# 5-Memory.net
KiCad netlist of a schematic drawn in Altium Designer
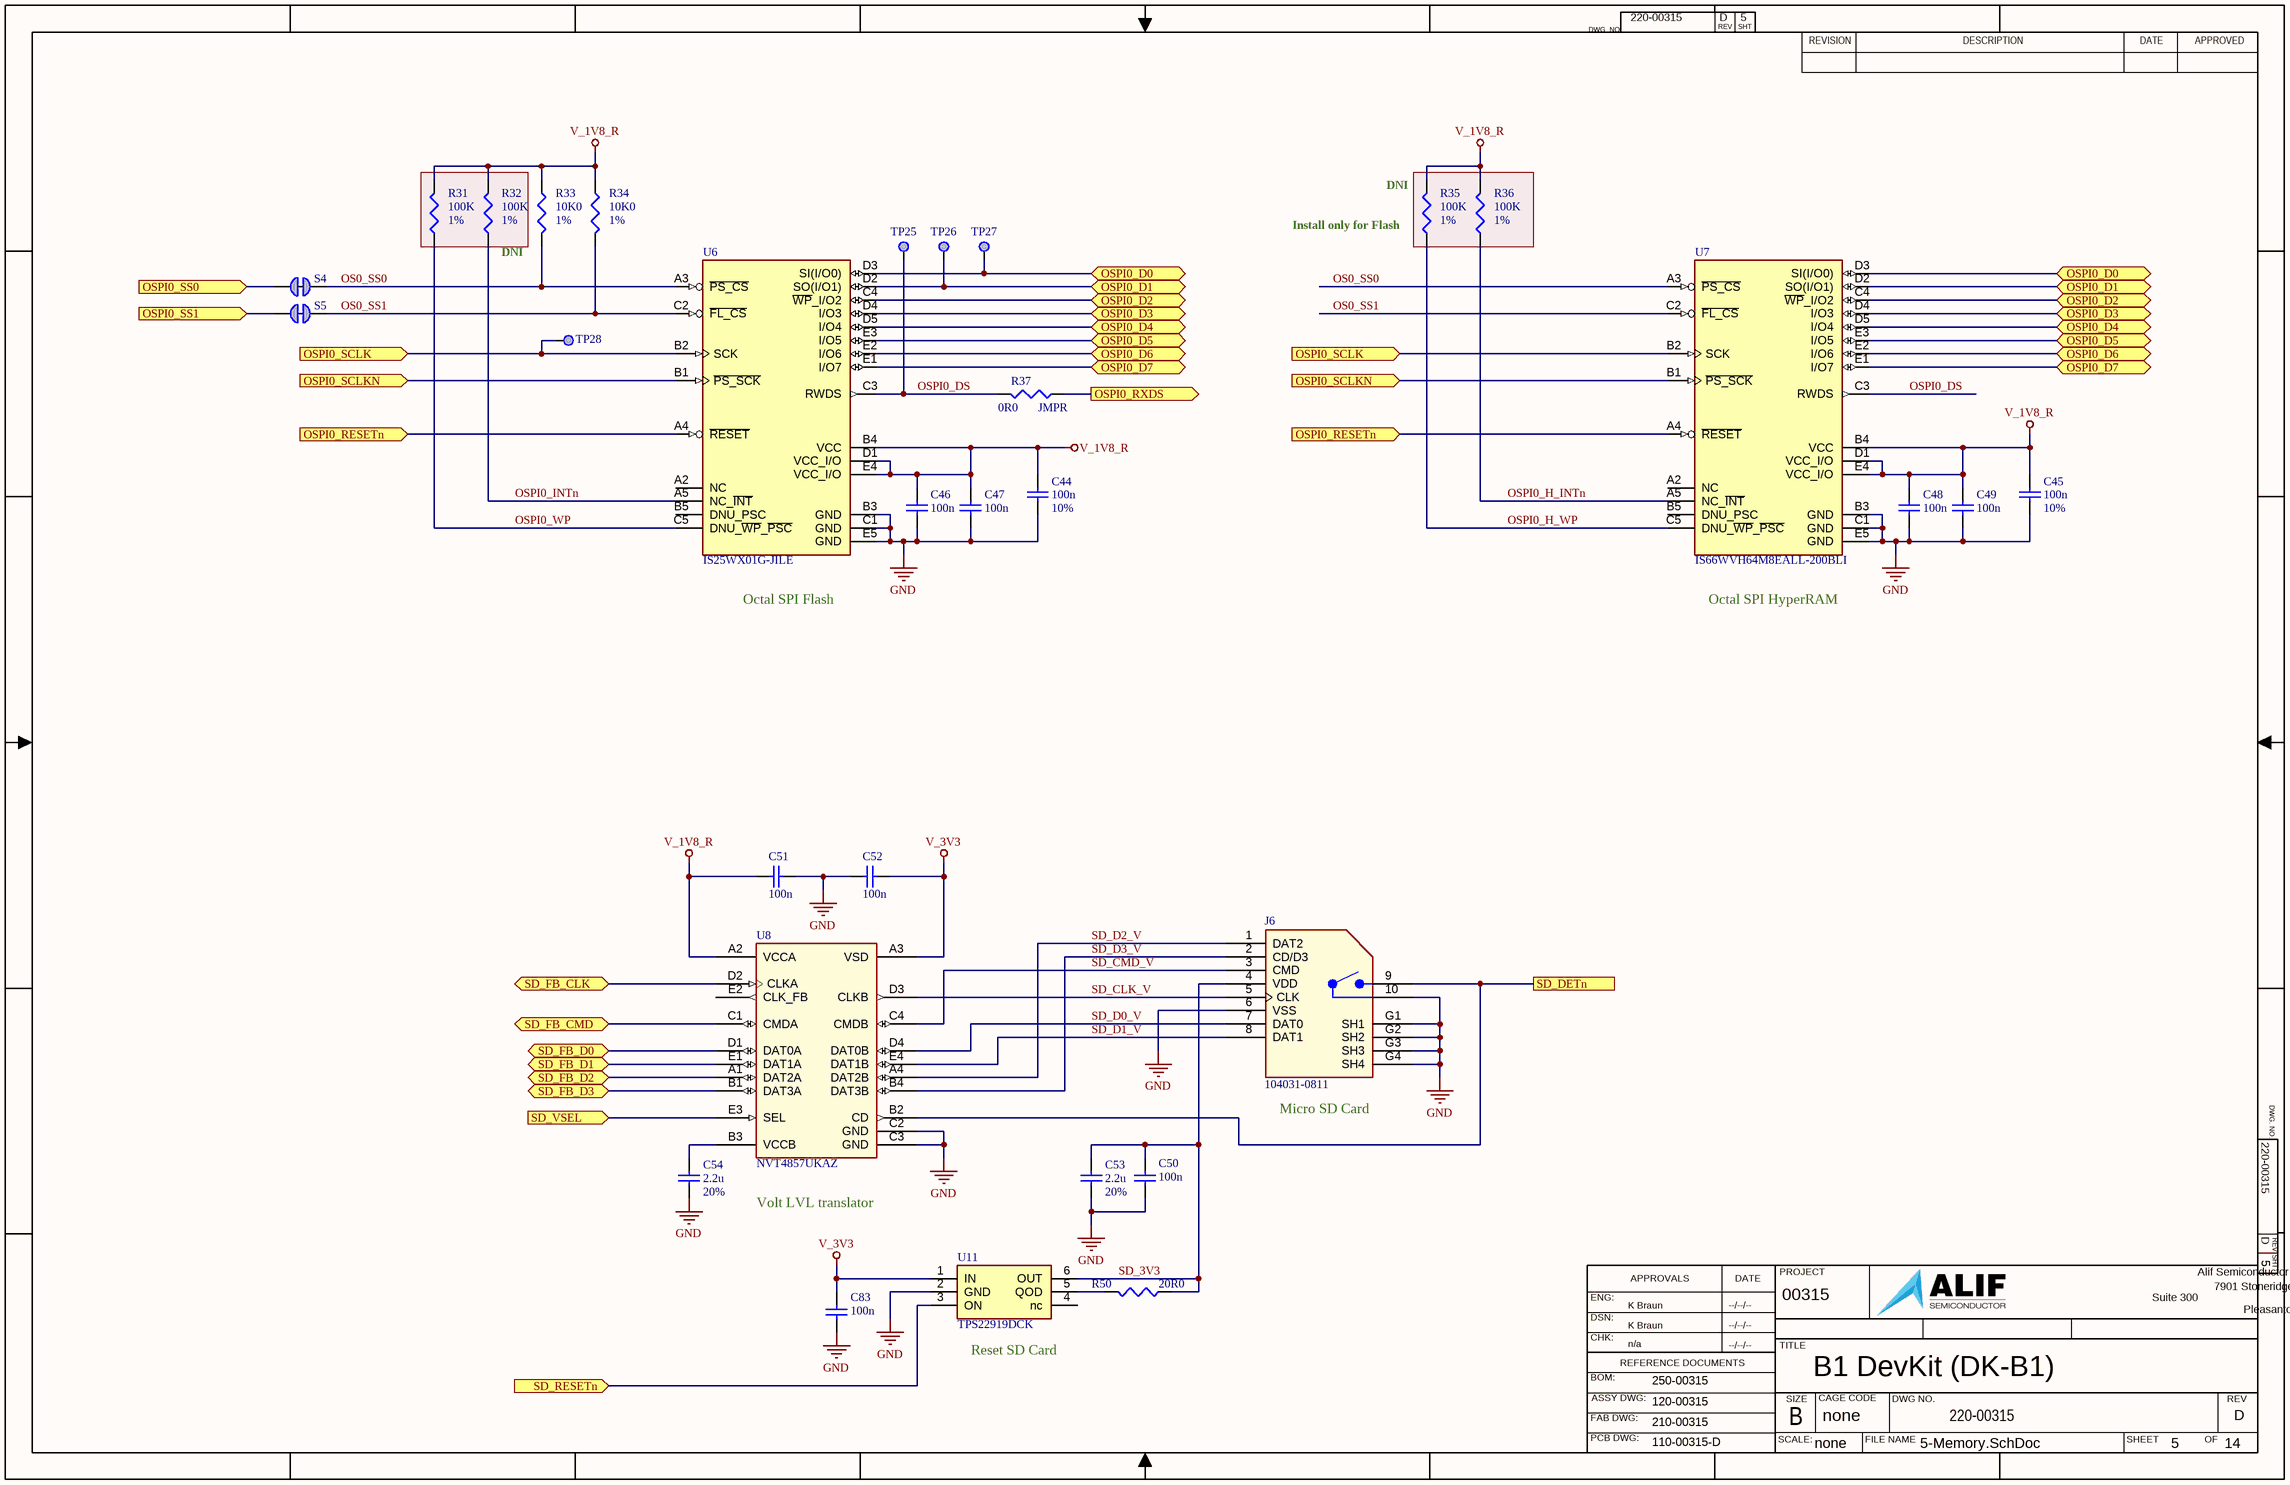
[diagram p0: 5-Memory.SchDoc]

(export (version "E")
  (design (tool "Eeschema 10.0.6"))
  (components
    (comp (ref "C44")
      (value "100n")
      (footprint "CAPC0402-01")
      (description "Cap,100nF,10%,50V,X7R,0402")
      (fields
        (field (name "VOLTAGE") "50V")
        (field (name "TOLERANCE") "10%")
        (field (name "Comment") "Cap")
        (field (name "PUBLISHER") "Altium Limited")
      )
      (libsource (lib "kb1") (part "Cap"))
    )
    (comp (ref "C45")
      (value "100n")
      (footprint "CAPC0402-01")
      (description "Cap,100nF,10%,50V,X7R,0402")
      (fields
        (field (name "VOLTAGE") "50V")
        (field (name "TOLERANCE") "10%")
        (field (name "Comment") "Cap")
        (field (name "PUBLISHER") "Altium Limited")
      )
      (libsource (lib "kb1") (part "Cap"))
    )
    (comp (ref "C46")
      (value "100n")
      (footprint "CAPC0402-01")
      (description "Cap,100nF,10%,50V,X7R,0402")
      (fields
        (field (name "VOLTAGE") "50V")
        (field (name "TOLERANCE") "10%")
        (field (name "PUBLISHER") "Altium Limited")
      )
      (libsource (lib "kb1") (part "Cap"))
    )
    (comp (ref "C47")
      (value "100n")
      (footprint "CAPC0402-01")
      (description "Cap,100nF,10%,50V,X7R,0402")
      (fields
        (field (name "VOLTAGE") "50V")
        (field (name "TOLERANCE") "10%")
        (field (name "PUBLISHER") "Altium Limited")
      )
      (libsource (lib "kb1") (part "Cap"))
    )
    (comp (ref "C48")
      (value "100n")
      (footprint "CAPC0402-01")
      (description "Cap,100nF,10%,50V,X7R,0402")
      (fields
        (field (name "VOLTAGE") "50V")
        (field (name "TOLERANCE") "10%")
        (field (name "PUBLISHER") "Altium Limited")
      )
      (libsource (lib "kb1") (part "Cap"))
    )
    (comp (ref "C49")
      (value "100n")
      (footprint "CAPC0402-01")
      (description "Cap,100nF,10%,50V,X7R,0402")
      (fields
        (field (name "VOLTAGE") "50V")
        (field (name "TOLERANCE") "10%")
        (field (name "PUBLISHER") "Altium Limited")
      )
      (libsource (lib "kb1") (part "Cap"))
    )
    (comp (ref "C50")
      (value "100n")
      (footprint "CAPC0402-01")
      (description "Cap,100nF,10%,50V,X7R,0402")
      (fields
        (field (name "VOLTAGE") "50V")
        (field (name "TOLERANCE") "10%")
        (field (name "PUBLISHER") "Altium Limited")
      )
      (libsource (lib "kb1") (part "Cap"))
    )
    (comp (ref "C51")
      (value "100n")
      (footprint "CAPC0402-01")
      (description "Cap,100nF,10%,50V,X7R,0402")
      (fields
        (field (name "VOLTAGE") "50V")
        (field (name "TOLERANCE") "10%")
        (field (name "PUBLISHER") "Altium Limited")
      )
      (libsource (lib "kb1") (part "Cap"))
    )
    (comp (ref "C52")
      (value "100n")
      (footprint "CAPC0402-01")
      (description "Cap,100nF,10%,50V,X7R,0402")
      (fields
        (field (name "VOLTAGE") "50V")
        (field (name "TOLERANCE") "10%")
        (field (name "PUBLISHER") "Altium Limited")
      )
      (libsource (lib "kb1") (part "Cap"))
    )
    (comp (ref "C53")
      (value "2.2u")
      (footprint "CAPC0402-01")
      (description "Cap,2.2uF,20%,25V,X5R,0402")
      (fields
        (field (name "VOLTAGE") "25V")
        (field (name "TOLERANCE") "20%")
        (field (name "Comment") "Cap_225M25VX5R0402_1")
        (field (name "PUBLISHER") "Altium Limited")
      )
      (libsource (lib "Alif-2") (part "Cap_225M25VX5R0402_1"))
    )
    (comp (ref "C54")
      (value "2.2u")
      (footprint "CAPC0402-01")
      (description "Cap,2.2uF,20%,25V,X5R,0402")
      (fields
        (field (name "VOLTAGE") "25V")
        (field (name "TOLERANCE") "20%")
        (field (name "Comment") "Cap_225M25VX5R0402_1")
        (field (name "PUBLISHER") "Altium Limited")
      )
      (libsource (lib "Alif-2") (part "Cap_225M25VX5R0402_1"))
    )
    (comp (ref "C83")
      (value "100n")
      (footprint "CAPC0402-01")
      (description "Cap,100nF,10%,50V,X7R,0402")
      (fields
        (field (name "VOLTAGE") "50V")
        (field (name "TOLERANCE") "10%")
        (field (name "PUBLISHER") "Altium Limited")
      )
      (libsource (lib "kb1") (part "Cap"))
    )
    (comp (ref "J6")
      (value "104031-0811")
      (footprint "CONN_SD_MOLEX_104031-0811")
      (description "Conn,Micro SD Card w/ switch, RA, 8-Pin SMD")
      (libsource (lib "Alif-2") (part "Conn_SD_Molex CN-SD-8-2SW-2S"))
    )
    (comp (ref "R31")
      (value "100K")
      (footprint "RESC0402-01")
      (description "DNI,Res,100K,1%,100ppm,0402")
      (fields
        (field (name "TOLERANCE") "1%")
        (field (name "Comment") "Res3")
        (field (name "PUBLISHER") "Altium Limited")
      )
      (libsource (lib "kb1") (part "Res3"))
    )
    (comp (ref "R32")
      (value "100K")
      (footprint "RESC0402-01")
      (description "DNI,Res,100K,1%,100ppm,0402")
      (fields
        (field (name "TOLERANCE") "1%")
        (field (name "Comment") "Res3")
        (field (name "PUBLISHER") "Altium Limited")
      )
      (libsource (lib "kb1") (part "Res3"))
    )
    (comp (ref "R33")
      (value "10K0")
      (footprint "RESC0402-01")
      (description "Res,10K0,1%,100ppm,0402")
      (fields
        (field (name "TOLERANCE") "1%")
        (field (name "Comment") "Res3")
        (field (name "PUBLISHER") "Altium Limited")
      )
      (libsource (lib "kb1") (part "Res3"))
    )
    (comp (ref "R34")
      (value "10K0")
      (footprint "RESC0402-01")
      (description "Res,10K0,1%,100ppm,0402")
      (fields
        (field (name "TOLERANCE") "1%")
        (field (name "Comment") "Res3")
        (field (name "PUBLISHER") "Altium Limited")
      )
      (libsource (lib "kb1") (part "Res3"))
    )
    (comp (ref "R35")
      (value "100K")
      (footprint "RESC0402-01")
      (description "DNI,Res,100K,1%,100ppm,0402")
      (fields
        (field (name "TOLERANCE") "1%")
        (field (name "Comment") "Res3")
        (field (name "PUBLISHER") "Altium Limited")
      )
      (libsource (lib "kb1") (part "Res3"))
    )
    (comp (ref "R36")
      (value "100K")
      (footprint "RESC0402-01")
      (description "DNI,Res,100K,1%,100ppm,0402")
      (fields
        (field (name "TOLERANCE") "1%")
        (field (name "Comment") "Res3")
        (field (name "PUBLISHER") "Altium Limited")
      )
      (libsource (lib "kb1") (part "Res3"))
    )
    (comp (ref "R37")
      (value "0R0")
      (footprint "RESC0402-01")
      (description "Res,0R ohm,Jumper,0402")
      (fields
        (field (name "TOLERANCE") "JMPR")
        (field (name "Comment") "Res3")
        (field (name "PUBLISHER") "Altium Limited")
      )
      (libsource (lib "kb1") (part "Res3"))
    )
    (comp (ref "R50")
      (value "20R0")
      (footprint "RESC0402-01")
      (description "Res,20R0,1%,100ppm,0402")
      (fields
        (field (name "TOLERANCE") "1%")
        (field (name "Comment") "Res3")
        (field (name "PUBLISHER") "Altium Limited")
      )
      (libsource (lib "kb1") (part "Res3"))
    )
    (comp (ref "S4")
      (value "SolderJumperShorted_Small")
      (footprint "Solderbridge_Shorted")
      (description "DNI,Solderable Jumper,Shorted")
      (fields (field (name "PUBLISHER") "Altium Limited"))
      (libsource (lib "Alif-2") (part "SolderJumperShorted_Small"))
    )
    (comp (ref "S5")
      (value "SolderJumperShorted_Small")
      (footprint "Solderbridge_Shorted")
      (description "DNI,Solderable Jumper,Shorted")
      (fields (field (name "PUBLISHER") "Altium Limited"))
      (libsource (lib "Alif-2") (part "SolderJumperShorted_Small"))
    )
    (comp (ref "TP25")
      (value "TP_SMPAD")
      (footprint "TP_30_RND")
      (description "Test Point, SMT Pad,--not a BOM item--")
      (libsource (lib "Alif-2") (part "TP_SMPAD"))
    )
    (comp (ref "TP26")
      (value "TP_SMPAD")
      (footprint "TP_30_RND")
      (description "Test Point, SMT Pad,--not a BOM item--")
      (libsource (lib "Alif-2") (part "TP_SMPAD"))
    )
    (comp (ref "TP27")
      (value "TP_SMPAD")
      (footprint "TP_30_RND")
      (description "Test Point, SMT Pad,--not a BOM item--")
      (libsource (lib "Alif-2") (part "TP_SMPAD"))
    )
    (comp (ref "TP28")
      (value "TP_SMPAD")
      (footprint "TP_30_RND")
      (description "Test Point, SMT Pad,--not a BOM item--")
      (libsource (lib "Alif-2") (part "TP_SMPAD"))
    )
    (comp (ref "U6")
      (value "IC_OctalSPI_Generic_1")
      (footprint "BGA24C100P5X5_800X600X100N")
      (description "IC, Flash,128MB x 8, Octal SPI, Ind Temp, 1.8V,24-BGA")
      (fields (field (name "MANUFACTURER PART NUMBER 1") "IS25WX01G-JILE"))
      (libsource (lib "Alif-2") (part "IC_OctalSPI_Generic_1"))
    )
    (comp (ref "U7")
      (value "IC_OctalSPI_Generic_1")
      (footprint "BGA24C100P5X5_800X600X100N")
      (description "IC, Hyper PSRAM,64MB x 8, Octal SPI, Ind Temp, 1.8V,24-BGA")
      (fields (field (name "MANUFACTURER PART NUMBER 1") "IS66WVH64M8EALL-200BLI"))
      (libsource (lib "Alif-2") (part "IC_OctalSPI_Generic_1"))
    )
    (comp (ref "U8")
      (value "NVT4857UKAZ")
      (footprint "WLCSP20_NVT4857_NXP")
      (libsource (lib "Alif-2") (part "IC_XLAT_NVT4857UK"))
    )
    (comp (ref "U11")
      (value "TPS22919DCK")
      (footprint "SOT363_DIO")
      (description "IC, Power Switch, Enable, Soft Start, Quick Discharge, 1.6V - 5.5V, 1.5A, SC-70 (SOT-363)")
      (libsource (lib "Alif-2") (part "IC_SWIT_TPS22919DCK"))
    )
  )
  (nets
    (net (code "1") (name "/OS0_SS0") (class "Default")
      (node (ref "R33") (pin "2") (pinfunction "2_2") (pintype "passive"))
      (node (ref "S4") (pin "2") (pinfunction "2_2") (pintype "passive"))
      (node (ref "U6") (pin "A3") (pinfunction "~{PS_CS}_A3") (pintype "input"))
      (node (ref "U7") (pin "A3") (pinfunction "~{PS_CS}_A3") (pintype "input"))
    )
    (net (code "2") (name "/OS0_SS1") (class "Default")
      (node (ref "R34") (pin "2") (pinfunction "2_2") (pintype "passive"))
      (node (ref "S5") (pin "2") (pinfunction "2_2") (pintype "passive"))
      (node (ref "U6") (pin "C2") (pinfunction "~{FL_CS}_C2") (pintype "input"))
      (node (ref "U7") (pin "C2") (pinfunction "~{FL_CS}_C2") (pintype "input"))
    )
    (net (code "3") (name "/OSPI0_D0") (class "Default")
      (node (ref "TP27") (pin "1") (pinfunction "1_1") (pintype "passive"))
      (node (ref "U6") (pin "D3") (pinfunction "SI(I/O0)_D3") (pintype "bidirectional"))
      (node (ref "U7") (pin "D3") (pinfunction "SI(I/O0)_D3") (pintype "bidirectional"))
    )
    (net (code "4") (name "/OSPI0_D1") (class "Default")
      (node (ref "TP26") (pin "1") (pinfunction "1_1") (pintype "passive"))
      (node (ref "U6") (pin "D2") (pinfunction "SO(I/O1)_D2") (pintype "bidirectional"))
      (node (ref "U7") (pin "D2") (pinfunction "SO(I/O1)_D2") (pintype "bidirectional"))
    )
    (net (code "5") (name "/OSPI0_D2") (class "Default")
      (node (ref "U6") (pin "C4") (pinfunction "~{WP}_I/O2_C4") (pintype "bidirectional"))
      (node (ref "U7") (pin "C4") (pinfunction "~{WP}_I/O2_C4") (pintype "bidirectional"))
    )
    (net (code "6") (name "/OSPI0_D3") (class "Default")
      (node (ref "U6") (pin "D4") (pinfunction "I/O3_D4") (pintype "bidirectional"))
      (node (ref "U7") (pin "D4") (pinfunction "I/O3_D4") (pintype "bidirectional"))
    )
    (net (code "7") (name "/OSPI0_D4") (class "Default")
      (node (ref "U6") (pin "D5") (pinfunction "I/O4_D5") (pintype "bidirectional"))
      (node (ref "U7") (pin "D5") (pinfunction "I/O4_D5") (pintype "bidirectional"))
    )
    (net (code "8") (name "/OSPI0_D5") (class "Default")
      (node (ref "U6") (pin "E3") (pinfunction "I/O5_E3") (pintype "bidirectional"))
      (node (ref "U7") (pin "E3") (pinfunction "I/O5_E3") (pintype "bidirectional"))
    )
    (net (code "9") (name "/OSPI0_D6") (class "Default")
      (node (ref "U6") (pin "E2") (pinfunction "I/O6_E2") (pintype "bidirectional"))
      (node (ref "U7") (pin "E2") (pinfunction "I/O6_E2") (pintype "bidirectional"))
    )
    (net (code "10") (name "/OSPI0_D7") (class "Default")
      (node (ref "U6") (pin "E1") (pinfunction "I/O7_E1") (pintype "bidirectional"))
      (node (ref "U7") (pin "E1") (pinfunction "I/O7_E1") (pintype "bidirectional"))
    )
    (net (code "11") (name "/OSPI0_DS") (class "Default")
      (node (ref "R37") (pin "2") (pinfunction "2_2") (pintype "passive"))
      (node (ref "TP25") (pin "1") (pinfunction "1_1") (pintype "passive"))
      (node (ref "U6") (pin "C3") (pinfunction "RWDS_C3") (pintype "output"))
      (node (ref "U7") (pin "C3") (pinfunction "RWDS_C3") (pintype "output"))
    )
    (net (code "12") (name "/OSPI0_H_INTn") (class "Default")
      (node (ref "R36") (pin "1") (pinfunction "1_1") (pintype "passive"))
      (node (ref "U7") (pin "A5") (pinfunction "NC_~{INT}_A5") (pintype "passive"))
    )
    (net (code "13") (name "/OSPI0_H_WP") (class "Default")
      (node (ref "R35") (pin "1") (pinfunction "1_1") (pintype "passive"))
      (node (ref "U7") (pin "C5") (pinfunction "DNU_~{WP}_~{PSC}_C5") (pintype "passive"))
    )
    (net (code "14") (name "/OSPI0_INTn") (class "Default")
      (node (ref "R32") (pin "1") (pinfunction "1_1") (pintype "passive"))
      (node (ref "U6") (pin "A5") (pinfunction "NC_~{INT}_A5") (pintype "passive"))
    )
    (net (code "15") (name "/OSPI0_RESETn") (class "Default")
      (node (ref "U6") (pin "A4") (pinfunction "~{RESET}_A4") (pintype "input"))
      (node (ref "U7") (pin "A4") (pinfunction "~{RESET}_A4") (pintype "input"))
    )
    (net (code "16") (name "/OSPI0_RXDS") (class "Default")
      (node (ref "R37") (pin "1") (pinfunction "1_1") (pintype "passive"))
    )
    (net (code "17") (name "/OSPI0_SCLK") (class "Default")
      (node (ref "TP28") (pin "1") (pinfunction "1_1") (pintype "passive"))
      (node (ref "U6") (pin "B2") (pinfunction "SCK_B2") (pintype "input"))
      (node (ref "U7") (pin "B2") (pinfunction "SCK_B2") (pintype "input"))
    )
    (net (code "18") (name "/OSPI0_SCLKN") (class "Default")
      (node (ref "U6") (pin "B1") (pinfunction "~{PS_SCK}_B1") (pintype "input"))
      (node (ref "U7") (pin "B1") (pinfunction "~{PS_SCK}_B1") (pintype "input"))
    )
    (net (code "19") (name "/OSPI0_SS0") (class "Default")
      (node (ref "S4") (pin "1") (pinfunction "1_1") (pintype "passive"))
    )
    (net (code "20") (name "/OSPI0_SS1") (class "Default")
      (node (ref "S5") (pin "1") (pinfunction "1_1") (pintype "passive"))
    )
    (net (code "21") (name "/OSPI0_WP") (class "Default")
      (node (ref "R31") (pin "1") (pinfunction "1_1") (pintype "passive"))
      (node (ref "U6") (pin "C5") (pinfunction "DNU_~{WP}_~{PSC}_C5") (pintype "passive"))
    )
    (net (code "22") (name "/SD_3V3") (class "Default")
      (node (ref "C50") (pin "2") (pinfunction "2_2") (pintype "passive"))
      (node (ref "C53") (pin "2") (pinfunction "2_2") (pintype "passive"))
      (node (ref "J6") (pin "4") (pinfunction "VDD_4") (pintype "passive"))
      (node (ref "R50") (pin "1") (pinfunction "1_1") (pintype "passive"))
      (node (ref "U11") (pin "6") (pinfunction "OUT_6") (pintype "passive"))
    )
    (net (code "23") (name "/SD_CLK_V") (class "Default")
      (node (ref "J6") (pin "5") (pinfunction "CLK_5") (pintype "passive"))
      (node (ref "U8") (pin "D3") (pinfunction "CLKB_D3") (pintype "output"))
    )
    (net (code "24") (name "/SD_CMD_V") (class "Default")
      (node (ref "J6") (pin "3") (pinfunction "CMD_3") (pintype "passive"))
      (node (ref "U8") (pin "C4") (pinfunction "CMDB_C4") (pintype "bidirectional"))
    )
    (net (code "25") (name "/SD_D0_V") (class "Default")
      (node (ref "J6") (pin "7") (pinfunction "DAT0_7") (pintype "passive"))
      (node (ref "U8") (pin "D4") (pinfunction "DAT0B_D4") (pintype "bidirectional"))
    )
    (net (code "26") (name "/SD_D1_V") (class "Default")
      (node (ref "J6") (pin "8") (pinfunction "DAT1_8") (pintype "passive"))
      (node (ref "U8") (pin "E4") (pinfunction "DAT1B_E4") (pintype "bidirectional"))
    )
    (net (code "27") (name "/SD_D2_V") (class "Default")
      (node (ref "J6") (pin "1") (pinfunction "DAT2_1") (pintype "passive"))
      (node (ref "U8") (pin "A4") (pinfunction "DAT2B_A4") (pintype "bidirectional"))
    )
    (net (code "28") (name "/SD_D3_V") (class "Default")
      (node (ref "J6") (pin "2") (pinfunction "CD/D3_2") (pintype "passive"))
      (node (ref "U8") (pin "B4") (pinfunction "DAT3B_B4") (pintype "bidirectional"))
    )
    (net (code "29") (name "/SD_DETn") (class "Default")
      (node (ref "J6") (pin "9") (pinfunction "CD_A_9") (pintype "passive"))
      (node (ref "U8") (pin "B2") (pinfunction "CD_B2") (pintype "output"))
    )
    (net (code "30") (name "/SD_FB_CLK") (class "Default")
      (node (ref "U8") (pin "D2") (pinfunction "CLKA_D2") (pintype "input"))
    )
    (net (code "31") (name "/SD_FB_CMD") (class "Default")
      (node (ref "U8") (pin "C1") (pinfunction "CMDA_C1") (pintype "bidirectional"))
    )
    (net (code "32") (name "/SD_FB_D0") (class "Default")
      (node (ref "U8") (pin "D1") (pinfunction "DAT0A_D1") (pintype "bidirectional"))
    )
    (net (code "33") (name "/SD_FB_D1") (class "Default")
      (node (ref "U8") (pin "E1") (pinfunction "DAT1A_E1") (pintype "bidirectional"))
    )
    (net (code "34") (name "/SD_FB_D2") (class "Default")
      (node (ref "U8") (pin "A1") (pinfunction "DAT2A_A1") (pintype "bidirectional"))
    )
    (net (code "35") (name "/SD_FB_D3") (class "Default")
      (node (ref "U8") (pin "B1") (pinfunction "DAT3A_B1") (pintype "bidirectional"))
    )
    (net (code "36") (name "/SD_RESETn") (class "Default")
      (node (ref "U11") (pin "3") (pinfunction "ON_3") (pintype "passive"))
    )
    (net (code "37") (name "/SD_VSEL") (class "Default")
      (node (ref "U8") (pin "E3") (pinfunction "SEL_E3") (pintype "input"))
    )
    (net (code "38") (name "GND") (class "Default")
      (node (ref "C44") (pin "1") (pinfunction "1_1") (pintype "passive"))
      (node (ref "C45") (pin "1") (pinfunction "1_1") (pintype "passive"))
      (node (ref "C46") (pin "1") (pinfunction "1_1") (pintype "passive"))
      (node (ref "C47") (pin "1") (pinfunction "1_1") (pintype "passive"))
      (node (ref "C48") (pin "1") (pinfunction "1_1") (pintype "passive"))
      (node (ref "C49") (pin "1") (pinfunction "1_1") (pintype "passive"))
      (node (ref "C50") (pin "1") (pinfunction "1_1") (pintype "passive"))
      (node (ref "C51") (pin "1") (pinfunction "1_1") (pintype "passive"))
      (node (ref "C52") (pin "2") (pinfunction "2_2") (pintype "passive"))
      (node (ref "C53") (pin "1") (pinfunction "1_1") (pintype "passive"))
      (node (ref "C54") (pin "1") (pinfunction "1_1") (pintype "passive"))
      (node (ref "C83") (pin "1") (pinfunction "1_1") (pintype "passive"))
      (node (ref "J6") (pin "10") (pinfunction "CD_B_10") (pintype "passive"))
      (node (ref "J6") (pin "6") (pinfunction "VSS_6") (pintype "passive"))
      (node (ref "J6") (pin "G1") (pinfunction "SH1_G1") (pintype "passive"))
      (node (ref "J6") (pin "G2") (pinfunction "SH2_G2") (pintype "passive"))
      (node (ref "J6") (pin "G3") (pinfunction "SH3_G3") (pintype "passive"))
      (node (ref "J6") (pin "G4") (pinfunction "SH4_G4") (pintype "passive"))
      (node (ref "U11") (pin "2") (pinfunction "GND_2") (pintype "passive"))
      (node (ref "U6") (pin "B3") (pinfunction "GND_B3") (pintype "power_in"))
      (node (ref "U6") (pin "C1") (pinfunction "GND_C1") (pintype "power_in"))
      (node (ref "U6") (pin "E5") (pinfunction "GND_E5") (pintype "power_in"))
      (node (ref "U7") (pin "B3") (pinfunction "GND_B3") (pintype "power_in"))
      (node (ref "U7") (pin "C1") (pinfunction "GND_C1") (pintype "power_in"))
      (node (ref "U7") (pin "E5") (pinfunction "GND_E5") (pintype "power_in"))
      (node (ref "U8") (pin "C2") (pinfunction "GND_C2") (pintype "power_in"))
      (node (ref "U8") (pin "C3") (pinfunction "GND_C3") (pintype "power_in"))
    )
    (net (code "39") (name "Net-(U8-VCCB)") (class "Default")
      (node (ref "C54") (pin "2") (pinfunction "2_2") (pintype "passive"))
      (node (ref "U8") (pin "B3") (pinfunction "VCCB_B3") (pintype "power_in"))
    )
    (net (code "40") (name "Net-(U11-QOD)") (class "Default")
      (node (ref "R50") (pin "2") (pinfunction "2_2") (pintype "passive"))
      (node (ref "U11") (pin "5") (pinfunction "QOD_5") (pintype "passive"))
    )
    (net (code "41") (name "V_1V8_R") (class "Default")
      (node (ref "C44") (pin "2") (pinfunction "2_2") (pintype "passive"))
      (node (ref "C45") (pin "2") (pinfunction "2_2") (pintype "passive"))
      (node (ref "C46") (pin "2") (pinfunction "2_2") (pintype "passive"))
      (node (ref "C47") (pin "2") (pinfunction "2_2") (pintype "passive"))
      (node (ref "C48") (pin "2") (pinfunction "2_2") (pintype "passive"))
      (node (ref "C49") (pin "2") (pinfunction "2_2") (pintype "passive"))
      (node (ref "C51") (pin "2") (pinfunction "2_2") (pintype "passive"))
      (node (ref "R31") (pin "2") (pinfunction "2_2") (pintype "passive"))
      (node (ref "R32") (pin "2") (pinfunction "2_2") (pintype "passive"))
      (node (ref "R33") (pin "1") (pinfunction "1_1") (pintype "passive"))
      (node (ref "R34") (pin "1") (pinfunction "1_1") (pintype "passive"))
      (node (ref "R35") (pin "2") (pinfunction "2_2") (pintype "passive"))
      (node (ref "R36") (pin "2") (pinfunction "2_2") (pintype "passive"))
      (node (ref "U6") (pin "B4") (pinfunction "VCC_B4") (pintype "power_in"))
      (node (ref "U6") (pin "D1") (pinfunction "VCC_I/O_D1") (pintype "power_in"))
      (node (ref "U6") (pin "E4") (pinfunction "VCC_I/O_E4") (pintype "power_in"))
      (node (ref "U7") (pin "B4") (pinfunction "VCC_B4") (pintype "power_in"))
      (node (ref "U7") (pin "D1") (pinfunction "VCC_I/O_D1") (pintype "power_in"))
      (node (ref "U7") (pin "E4") (pinfunction "VCC_I/O_E4") (pintype "power_in"))
      (node (ref "U8") (pin "A2") (pinfunction "VCCA_A2") (pintype "power_in"))
    )
    (net (code "42") (name "V_3V3") (class "Default")
      (node (ref "C52") (pin "1") (pinfunction "1_1") (pintype "passive"))
      (node (ref "C83") (pin "2") (pinfunction "2_2") (pintype "passive"))
      (node (ref "U11") (pin "1") (pinfunction "IN_1") (pintype "passive"))
      (node (ref "U8") (pin "A3") (pinfunction "VSD_A3") (pintype "power_in"))
    )
    (net (code "43") (name "unconnected-(U6-DNU_PSC-PadB5)") (class "Default")
      (node (ref "U6") (pin "B5") (pinfunction "DNU_PSC_B5") (pintype "passive"))
    )
    (net (code "44") (name "unconnected-(U6-NC-PadA2)") (class "Default")
      (node (ref "U6") (pin "A2") (pinfunction "NC_A2") (pintype "passive"))
    )
    (net (code "45") (name "unconnected-(U7-DNU_PSC-PadB5)") (class "Default")
      (node (ref "U7") (pin "B5") (pinfunction "DNU_PSC_B5") (pintype "passive"))
    )
    (net (code "46") (name "unconnected-(U7-NC-PadA2)") (class "Default")
      (node (ref "U7") (pin "A2") (pinfunction "NC_A2") (pintype "passive"))
    )
    (net (code "47") (name "unconnected-(U8-CLK_FB-PadE2)") (class "Default")
      (node (ref "U8") (pin "E2") (pinfunction "CLK_FB_E2") (pintype "output"))
    )
    (net (code "48") (name "unconnected-(U11-nc-Pad4)") (class "Default")
      (node (ref "U11") (pin "4") (pinfunction "nc_4") (pintype "passive"))
    )
  )
)
